# Input_channel.net
KiCad netlist of a schematic drawn in Altium Designer
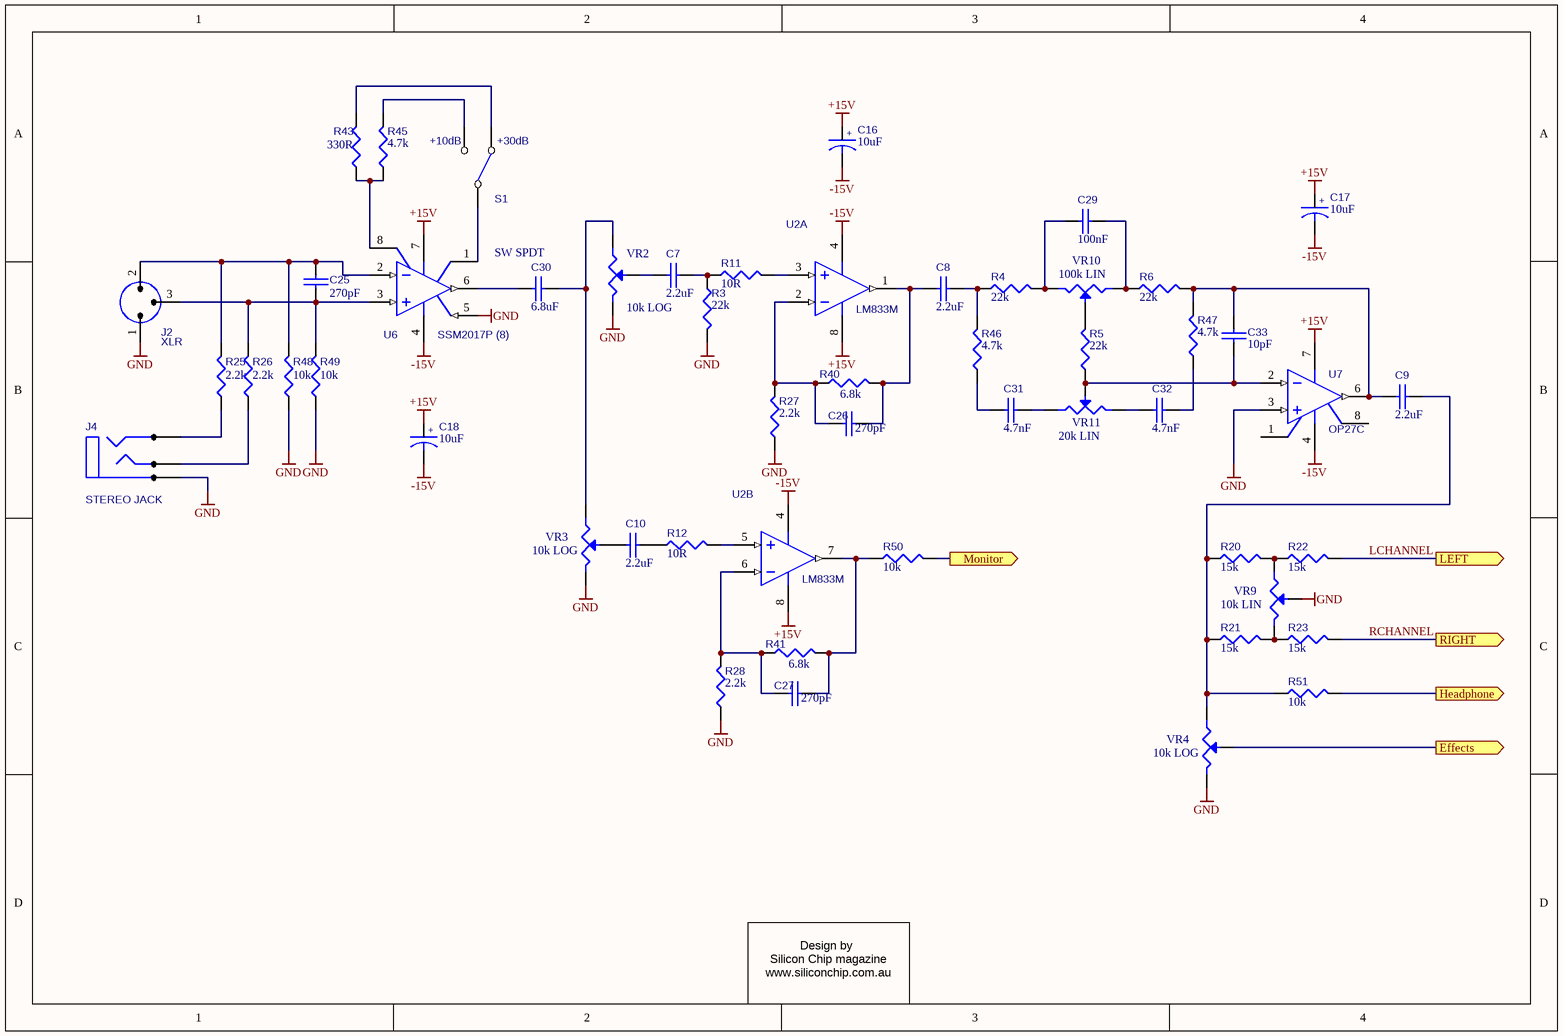
[diagram p0: Input channel.SchDoc]

(export (version "E")
  (design (tool "Eeschema 10.0.6"))
  (components
    (comp (ref "C7")
      (value "2.2uF")
      (footprint "RB.2/.4-NP")
      (description "Capacitor")
      (libsource (lib "*") (part "CAP"))
    )
    (comp (ref "C8")
      (value "2.2uF")
      (footprint "RB.2/.4-NP")
      (description "Capacitor")
      (libsource (lib "*") (part "CAP"))
    )
    (comp (ref "C9")
      (value "2.2uF")
      (footprint "RB.2/.4-NP")
      (description "Capacitor")
      (libsource (lib "*") (part "CAP"))
    )
    (comp (ref "C10")
      (value "2.2uF")
      (footprint "RB.2/.4-NP")
      (description "Capacitor")
      (libsource (lib "*") (part "CAP"))
    )
    (comp (ref "C16")
      (value "10uF")
      (footprint "RB.2/.4")
      (description "Bi-Polar Capacitor")
      (libsource (lib "*") (part "CAPACITOR POL"))
    )
    (comp (ref "C17")
      (value "10uF")
      (footprint "RB.2/.4")
      (description "Bi-Polar Capacitor")
      (libsource (lib "*") (part "CAPACITOR POL"))
    )
    (comp (ref "C18")
      (value "10uF")
      (footprint "RB.2/.4")
      (description "Bi-Polar Capacitor")
      (libsource (lib "*") (part "CAPACITOR POL"))
    )
    (comp (ref "C25")
      (value "270pF")
      (footprint "RAD0.2")
      (description "Capacitor")
      (libsource (lib "*") (part "CAP"))
    )
    (comp (ref "C26")
      (value "270pF")
      (footprint "RAD0.2")
      (description "Capacitor")
      (libsource (lib "*") (part "CAP"))
    )
    (comp (ref "C27")
      (value "270pF")
      (footprint "RAD0.2")
      (description "Capacitor")
      (libsource (lib "*") (part "CAP"))
    )
    (comp (ref "C29")
      (value "100nF")
      (footprint "RAD0.2")
      (description "Capacitor")
      (libsource (lib "*") (part "CAP"))
    )
    (comp (ref "C30")
      (value "6.8uF")
      (footprint "RB.2/.4-NP")
      (description "Capacitor")
      (libsource (lib "*") (part "CAP"))
    )
    (comp (ref "C31")
      (value "4.7nF")
      (footprint "RAD0.2")
      (description "Capacitor")
      (libsource (lib "*") (part "CAP"))
    )
    (comp (ref "C32")
      (value "4.7nF")
      (footprint "RAD0.2")
      (description "Capacitor")
      (libsource (lib "*") (part "CAP"))
    )
    (comp (ref "C33")
      (value "10pF")
      (footprint "RAD0.2")
      (description "Capacitor")
      (libsource (lib "*") (part "CAP"))
    )
    (comp (ref "J2")
      (value "XLR")
      (footprint "XLR-FEMALE")
      (description "XLR connector, PCB mounted")
      (libsource (lib "*") (part "XLR"))
    )
    (comp (ref "J4")
      (value "STEREO JACK")
      (footprint "JACK-6.25MM")
      (libsource (lib "*") (part "PHONEJACK STEREO"))
    )
    (comp (ref "R3")
      (value "22k")
      (footprint "AXIAL0.4")
      (description "Resistor")
      (libsource (lib "") (part "RES1_2"))
    )
    (comp (ref "R4")
      (value "22k")
      (footprint "AXIAL0.4")
      (description "Resistor")
      (libsource (lib "*") (part "RES1"))
    )
    (comp (ref "R5")
      (value "22k")
      (footprint "AXIAL0.4")
      (description "Resistor")
      (libsource (lib "") (part "RES1_1"))
    )
    (comp (ref "R6")
      (value "22k")
      (footprint "AXIAL0.4")
      (description "Resistor")
      (libsource (lib "*") (part "RES1"))
    )
    (comp (ref "R11")
      (value "10R")
      (footprint "AXIAL0.4")
      (description "Resistor")
      (libsource (lib "*") (part "RES1"))
    )
    (comp (ref "R12")
      (value "10R")
      (footprint "AXIAL0.4")
      (description "Resistor")
      (libsource (lib "*") (part "RES1"))
    )
    (comp (ref "R20")
      (value "15k")
      (footprint "AXIAL0.4")
      (description "Resistor")
      (libsource (lib "*") (part "RES1"))
    )
    (comp (ref "R21")
      (value "15k")
      (footprint "AXIAL0.4")
      (description "Resistor")
      (libsource (lib "*") (part "RES1"))
    )
    (comp (ref "R22")
      (value "15k")
      (footprint "AXIAL0.4")
      (description "Resistor")
      (libsource (lib "*") (part "RES1"))
    )
    (comp (ref "R23")
      (value "15k")
      (footprint "AXIAL0.4")
      (description "Resistor")
      (libsource (lib "*") (part "RES1"))
    )
    (comp (ref "R25")
      (value "2.2k")
      (footprint "AXIAL0.4")
      (description "Resistor")
      (libsource (lib "") (part "RES1_1"))
    )
    (comp (ref "R26")
      (value "2.2k")
      (footprint "AXIAL0.4")
      (description "Resistor")
      (libsource (lib "") (part "RES1_1"))
    )
    (comp (ref "R27")
      (value "2.2k")
      (footprint "AXIAL0.4")
      (description "Resistor")
      (libsource (lib "") (part "RES1_1"))
    )
    (comp (ref "R28")
      (value "2.2k")
      (footprint "AXIAL0.4")
      (description "Resistor")
      (libsource (lib "") (part "RES1_1"))
    )
    (comp (ref "R40")
      (value "6.8k")
      (footprint "AXIAL0.4")
      (description "Resistor")
      (libsource (lib "*") (part "RES1"))
    )
    (comp (ref "R41")
      (value "6.8k")
      (footprint "AXIAL0.4")
      (description "Resistor")
      (libsource (lib "*") (part "RES1"))
    )
    (comp (ref "R43")
      (value "330R")
      (footprint "AXIAL0.4")
      (description "Resistor")
      (libsource (lib "") (part "RES1_1"))
    )
    (comp (ref "R45")
      (value "4.7k")
      (footprint "AXIAL0.4")
      (description "Resistor")
      (libsource (lib "") (part "RES1_1"))
    )
    (comp (ref "R46")
      (value "4.7k")
      (footprint "AXIAL0.4")
      (description "Resistor")
      (libsource (lib "") (part "RES1_1"))
    )
    (comp (ref "R47")
      (value "4.7k")
      (footprint "AXIAL0.4")
      (description "Resistor")
      (libsource (lib "") (part "RES1_1"))
    )
    (comp (ref "R48")
      (value "10k")
      (footprint "AXIAL0.4")
      (description "Resistor")
      (libsource (lib "") (part "RES1_1"))
    )
    (comp (ref "R49")
      (value "10k")
      (footprint "AXIAL0.4")
      (description "Resistor")
      (libsource (lib "") (part "RES1_1"))
    )
    (comp (ref "R50")
      (value "10k")
      (footprint "AXIAL0.4")
      (description "Resistor")
      (libsource (lib "*") (part "RES1"))
    )
    (comp (ref "R51")
      (value "10k")
      (footprint "AXIAL0.4")
      (description "Resistor")
      (libsource (lib "*") (part "RES1"))
    )
    (comp (ref "S1") (value "SW SPDT") (footprint "SW-SPDT") (libsource (lib "Mixer") (part "SW SPDT")))
    (comp (ref "U2")
      (value "LM833M")
      (footprint "DIP8")
      (description "Fast Settling Dual Operational Amplifier")
      (libsource (lib "*") (part "LM833M"))
    )
    (comp (ref "U6")
      (value "SSM2017P (8)")
      (footprint "DIP8")
      (description "Self-Contained Audio Preamplifier")
      (libsource (lib "*") (part "SSM2017P (8)"))
    )
    (comp (ref "U7")
      (value "OP27C")
      (footprint "DIP8")
      (description "Low Noise, High Speed Precision Operational Amplifier")
      (libsource (lib "*") (part "OP27C"))
    )
    (comp (ref "VR2")
      (value "10k LOG")
      (footprint "POT - 24MM")
      (description "Potentiometer")
      (libsource (lib "*") (part "POT1"))
    )
    (comp (ref "VR3")
      (value "10k LOG")
      (footprint "POT - 24MM")
      (description "Potentiometer")
      (libsource (lib "*") (part "POT1"))
    )
    (comp (ref "VR4")
      (value "10k LOG")
      (footprint "POT - 24MM")
      (description "Potentiometer")
      (libsource (lib "*") (part "POT1"))
    )
    (comp (ref "VR9")
      (value "10k LIN")
      (footprint "POT - 24MM")
      (description "Potentiometer")
      (libsource (lib "*") (part "POT1"))
    )
    (comp (ref "VR10")
      (value "100k LIN")
      (footprint "POT - 24MM")
      (description "Potentiometer")
      (libsource (lib "*") (part "POT1"))
    )
    (comp (ref "VR11")
      (value "20k LIN")
      (footprint "POT - 24MM")
      (description "Potentiometer")
      (libsource (lib "*") (part "POT1"))
    )
  )
  (nets
    (net (code "1") (name "+15V") (class "Default")
      (node (ref "C16") (pin "1") (pinfunction "1_1") (pintype "passive"))
      (node (ref "C17") (pin "1") (pinfunction "1_1") (pintype "passive"))
      (node (ref "C18") (pin "1") (pinfunction "1_1") (pintype "passive"))
      (node (ref "U2") (pin "8") (pinfunction "V+_8") (pintype "power_in"))
      (node (ref "U6") (pin "7") (pinfunction "V+_7") (pintype "power_in"))
      (node (ref "U7") (pin "7") (pinfunction "V+_7") (pintype "power_in"))
    )
    (net (code "2") (name "-15V") (class "Default")
      (node (ref "C16") (pin "2") (pinfunction "2_2") (pintype "passive"))
      (node (ref "C17") (pin "2") (pinfunction "2_2") (pintype "passive"))
      (node (ref "C18") (pin "2") (pinfunction "2_2") (pintype "passive"))
      (node (ref "U2") (pin "4") (pinfunction "V-_4") (pintype "power_in"))
      (node (ref "U6") (pin "4") (pinfunction "V-_4") (pintype "power_in"))
      (node (ref "U7") (pin "4") (pinfunction "V-_4") (pintype "power_in"))
    )
    (net (code "3") (name "/Effects") (class "Default")
      (node (ref "VR4") (pin "2") (pinfunction "W_2") (pintype "passive"))
    )
    (net (code "4") (name "/Headphone") (class "Default")
      (node (ref "R51") (pin "2") (pinfunction "2_2") (pintype "passive"))
    )
    (net (code "5") (name "/LCHANNEL") (class "Default")
      (node (ref "R22") (pin "2") (pinfunction "2_2") (pintype "passive"))
    )
    (net (code "6") (name "/Monitor") (class "Default")
      (node (ref "R50") (pin "2") (pinfunction "2_2") (pintype "passive"))
    )
    (net (code "7") (name "/RCHANNEL") (class "Default")
      (node (ref "R23") (pin "2") (pinfunction "2_2") (pintype "passive"))
    )
    (net (code "8") (name "GND") (class "Default")
      (node (ref "J2") (pin "1") (pinfunction "1_1") (pintype "passive"))
      (node (ref "J4") (pin "3") (pinfunction "C_3") (pintype "passive"))
      (node (ref "R27") (pin "1") (pinfunction "1_1") (pintype "passive"))
      (node (ref "R28") (pin "1") (pinfunction "1_1") (pintype "passive"))
      (node (ref "R3") (pin "2") (pinfunction "2_2") (pintype "passive"))
      (node (ref "R48") (pin "1") (pinfunction "1_1") (pintype "passive"))
      (node (ref "R49") (pin "1") (pinfunction "1_1") (pintype "passive"))
      (node (ref "U6") (pin "5") (pinfunction "REF_5") (pintype "input"))
      (node (ref "U7") (pin "3") (pinfunction "+IN_3") (pintype "input"))
      (node (ref "VR2") (pin "3") (pinfunction "3_3") (pintype "passive"))
      (node (ref "VR3") (pin "3") (pinfunction "3_3") (pintype "passive"))
      (node (ref "VR4") (pin "3") (pinfunction "3_3") (pintype "passive"))
      (node (ref "VR9") (pin "2") (pinfunction "W_2") (pintype "passive"))
    )
    (net (code "9") (name "Net-(C7-Pad2)") (class "Default")
      (node (ref "C7") (pin "2") (pinfunction "2_2") (pintype "passive"))
      (node (ref "R11") (pin "1") (pinfunction "1_1") (pintype "passive"))
      (node (ref "R3") (pin "1") (pinfunction "1_1") (pintype "passive"))
    )
    (net (code "10") (name "Net-(C8-Pad2)") (class "Default")
      (node (ref "C8") (pin "2") (pinfunction "2_2") (pintype "passive"))
      (node (ref "R4") (pin "1") (pinfunction "1_1") (pintype "passive"))
      (node (ref "R46") (pin "2") (pinfunction "2_2") (pintype "passive"))
    )
    (net (code "11") (name "Net-(C9-Pad2)") (class "Default")
      (node (ref "C9") (pin "2") (pinfunction "2_2") (pintype "passive"))
      (node (ref "R20") (pin "1") (pinfunction "1_1") (pintype "passive"))
      (node (ref "R21") (pin "1") (pinfunction "1_1") (pintype "passive"))
      (node (ref "R51") (pin "1") (pinfunction "1_1") (pintype "passive"))
      (node (ref "VR4") (pin "1") (pinfunction "1_1") (pintype "passive"))
    )
    (net (code "12") (name "Net-(C10-Pad2)") (class "Default")
      (node (ref "C10") (pin "2") (pinfunction "2_2") (pintype "passive"))
      (node (ref "R12") (pin "1") (pinfunction "1_1") (pintype "passive"))
    )
    (net (code "13") (name "Net-(C29-Pad1)") (class "Default")
      (node (ref "C29") (pin "1") (pinfunction "1_1") (pintype "passive"))
      (node (ref "R4") (pin "2") (pinfunction "2_2") (pintype "passive"))
      (node (ref "VR10") (pin "3") (pinfunction "3_3") (pintype "passive"))
    )
    (net (code "14") (name "Net-(C29-Pad2)") (class "Default")
      (node (ref "C29") (pin "2") (pinfunction "2_2") (pintype "passive"))
      (node (ref "R6") (pin "1") (pinfunction "1_1") (pintype "passive"))
      (node (ref "VR10") (pin "1") (pinfunction "1_1") (pintype "passive"))
    )
    (net (code "15") (name "Net-(C30-Pad2)") (class "Default")
      (node (ref "C30") (pin "2") (pinfunction "2_2") (pintype "passive"))
      (node (ref "VR2") (pin "1") (pinfunction "1_1") (pintype "passive"))
      (node (ref "VR3") (pin "1") (pinfunction "1_1") (pintype "passive"))
    )
    (net (code "16") (name "Net-(C31-Pad1)") (class "Default")
      (node (ref "C31") (pin "1") (pinfunction "1_1") (pintype "passive"))
      (node (ref "R46") (pin "1") (pinfunction "1_1") (pintype "passive"))
    )
    (net (code "17") (name "Net-(C31-Pad2)") (class "Default")
      (node (ref "C31") (pin "2") (pinfunction "2_2") (pintype "passive"))
      (node (ref "VR11") (pin "1") (pinfunction "1_1") (pintype "passive"))
    )
    (net (code "18") (name "Net-(C32-Pad1)") (class "Default")
      (node (ref "C32") (pin "1") (pinfunction "1_1") (pintype "passive"))
      (node (ref "VR11") (pin "3") (pinfunction "3_3") (pintype "passive"))
    )
    (net (code "19") (name "Net-(C32-Pad2)") (class "Default")
      (node (ref "C32") (pin "2") (pinfunction "2_2") (pintype "passive"))
      (node (ref "R47") (pin "1") (pinfunction "1_1") (pintype "passive"))
    )
    (net (code "20") (name "Net-(J4-A)") (class "Default")
      (node (ref "J4") (pin "1") (pinfunction "A_1") (pintype "passive"))
      (node (ref "R25") (pin "1") (pinfunction "1_1") (pintype "passive"))
    )
    (net (code "21") (name "Net-(J4-B)") (class "Default")
      (node (ref "J4") (pin "2") (pinfunction "B_2") (pintype "passive"))
      (node (ref "R26") (pin "1") (pinfunction "1_1") (pintype "passive"))
    )
    (net (code "22") (name "Net-(R20-Pad2)") (class "Default")
      (node (ref "R20") (pin "2") (pinfunction "2_2") (pintype "passive"))
      (node (ref "R22") (pin "1") (pinfunction "1_1") (pintype "passive"))
      (node (ref "VR9") (pin "1") (pinfunction "1_1") (pintype "passive"))
    )
    (net (code "23") (name "Net-(R21-Pad2)") (class "Default")
      (node (ref "R21") (pin "2") (pinfunction "2_2") (pintype "passive"))
      (node (ref "R23") (pin "1") (pinfunction "1_1") (pintype "passive"))
      (node (ref "VR9") (pin "3") (pinfunction "3_3") (pintype "passive"))
    )
    (net (code "24") (name "Net-(S1-COMMON)") (class "Default")
      (node (ref "S1") (pin "1") (pinfunction "COMMON_1") (pintype "passive"))
      (node (ref "U6") (pin "1") (pinfunction "RG1_1") (pintype "passive"))
    )
    (net (code "25") (name "Net-(S1-NC)") (class "Default")
      (node (ref "R43") (pin "2") (pinfunction "2_2") (pintype "passive"))
      (node (ref "S1") (pin "2") (pinfunction "NC_2") (pintype "passive"))
    )
    (net (code "26") (name "Net-(S1-NO)") (class "Default")
      (node (ref "R45") (pin "2") (pinfunction "2_2") (pintype "passive"))
      (node (ref "S1") (pin "3") (pinfunction "NO_3") (pintype "passive"))
    )
    (net (code "27") (name "Net-(U2A-IN1+)") (class "Default")
      (node (ref "R11") (pin "2") (pinfunction "2_2") (pintype "passive"))
      (node (ref "U2") (pin "3") (pinfunction "IN1+_3") (pintype "input"))
    )
    (net (code "28") (name "Net-(U2A-IN1-)") (class "Default")
      (node (ref "C26") (pin "1") (pinfunction "1_1") (pintype "passive"))
      (node (ref "R27") (pin "2") (pinfunction "2_2") (pintype "passive"))
      (node (ref "R40") (pin "1") (pinfunction "1_1") (pintype "passive"))
      (node (ref "U2") (pin "2") (pinfunction "IN1-_2") (pintype "input"))
    )
    (net (code "29") (name "Net-(U2A-OUT1)") (class "Default")
      (node (ref "C26") (pin "2") (pinfunction "2_2") (pintype "passive"))
      (node (ref "C8") (pin "1") (pinfunction "1_1") (pintype "passive"))
      (node (ref "R40") (pin "2") (pinfunction "2_2") (pintype "passive"))
      (node (ref "U2") (pin "1") (pinfunction "OUT1_1") (pintype "output"))
    )
    (net (code "30") (name "Net-(U2B-IN2+)") (class "Default")
      (node (ref "R12") (pin "2") (pinfunction "2_2") (pintype "passive"))
      (node (ref "U2") (pin "5") (pinfunction "IN2+_5") (pintype "input"))
    )
    (net (code "31") (name "Net-(U2B-IN2-)") (class "Default")
      (node (ref "C27") (pin "1") (pinfunction "1_1") (pintype "passive"))
      (node (ref "R28") (pin "2") (pinfunction "2_2") (pintype "passive"))
      (node (ref "R41") (pin "1") (pinfunction "1_1") (pintype "passive"))
      (node (ref "U2") (pin "6") (pinfunction "IN2-_6") (pintype "input"))
    )
    (net (code "32") (name "Net-(U2B-OUT2)") (class "Default")
      (node (ref "C27") (pin "2") (pinfunction "2_2") (pintype "passive"))
      (node (ref "R41") (pin "2") (pinfunction "2_2") (pintype "passive"))
      (node (ref "R50") (pin "1") (pinfunction "1_1") (pintype "passive"))
      (node (ref "U2") (pin "7") (pinfunction "OUT2_7") (pintype "output"))
    )
    (net (code "33") (name "Net-(U6-IN+)") (class "Default")
      (node (ref "C25") (pin "2") (pinfunction "2_2") (pintype "passive"))
      (node (ref "J2") (pin "3") (pinfunction "3_3") (pintype "passive"))
      (node (ref "R26") (pin "2") (pinfunction "2_2") (pintype "passive"))
      (node (ref "R49") (pin "2") (pinfunction "2_2") (pintype "passive"))
      (node (ref "U6") (pin "3") (pinfunction "IN+_3") (pintype "input"))
    )
    (net (code "34") (name "Net-(U6-IN-)") (class "Default")
      (node (ref "C25") (pin "1") (pinfunction "1_1") (pintype "passive"))
      (node (ref "J2") (pin "2") (pinfunction "2_2") (pintype "passive"))
      (node (ref "R25") (pin "2") (pinfunction "2_2") (pintype "passive"))
      (node (ref "R48") (pin "2") (pinfunction "2_2") (pintype "passive"))
      (node (ref "U6") (pin "2") (pinfunction "IN-_2") (pintype "input"))
    )
    (net (code "35") (name "Net-(U6-OUT)") (class "Default")
      (node (ref "C30") (pin "1") (pinfunction "1_1") (pintype "passive"))
      (node (ref "U6") (pin "6") (pinfunction "OUT_6") (pintype "output"))
    )
    (net (code "36") (name "Net-(U6-RG2)") (class "Default")
      (node (ref "R43") (pin "1") (pinfunction "1_1") (pintype "passive"))
      (node (ref "R45") (pin "1") (pinfunction "1_1") (pintype "passive"))
      (node (ref "U6") (pin "8") (pinfunction "RG2_8") (pintype "passive"))
    )
    (net (code "37") (name "Net-(U7--IN)") (class "Default")
      (node (ref "C33") (pin "1") (pinfunction "1_1") (pintype "passive"))
      (node (ref "R5") (pin "1") (pinfunction "1_1") (pintype "passive"))
      (node (ref "U7") (pin "2") (pinfunction "-IN_2") (pintype "input"))
      (node (ref "VR11") (pin "2") (pinfunction "W_2") (pintype "passive"))
    )
    (net (code "38") (name "Net-(U7-OUT)") (class "Default")
      (node (ref "C33") (pin "2") (pinfunction "2_2") (pintype "passive"))
      (node (ref "C9") (pin "1") (pinfunction "1_1") (pintype "passive"))
      (node (ref "R47") (pin "2") (pinfunction "2_2") (pintype "passive"))
      (node (ref "R6") (pin "2") (pinfunction "2_2") (pintype "passive"))
      (node (ref "U7") (pin "6") (pinfunction "OUT_6") (pintype "output"))
    )
    (net (code "39") (name "Net-(VR2-W)") (class "Default")
      (node (ref "C7") (pin "1") (pinfunction "1_1") (pintype "passive"))
      (node (ref "VR2") (pin "2") (pinfunction "W_2") (pintype "passive"))
    )
    (net (code "40") (name "Net-(VR3-W)") (class "Default")
      (node (ref "C10") (pin "1") (pinfunction "1_1") (pintype "passive"))
      (node (ref "VR3") (pin "2") (pinfunction "W_2") (pintype "passive"))
    )
    (net (code "41") (name "Net-(VR10-W)") (class "Default")
      (node (ref "R5") (pin "2") (pinfunction "2_2") (pintype "passive"))
      (node (ref "VR10") (pin "2") (pinfunction "W_2") (pintype "passive"))
    )
    (net (code "42") (name "unconnected-(U7-TRIM-Pad1)") (class "Default")
      (node (ref "U7") (pin "1") (pinfunction "TRIM_1") (pintype "passive"))
    )
    (net (code "43") (name "unconnected-(U7-TRIM-Pad8)") (class "Default")
      (node (ref "U7") (pin "8") (pinfunction "TRIM_8") (pintype "passive"))
    )
  )
)
